# H1BR61.net
KiCad netlist of a schematic drawn in EAGLE
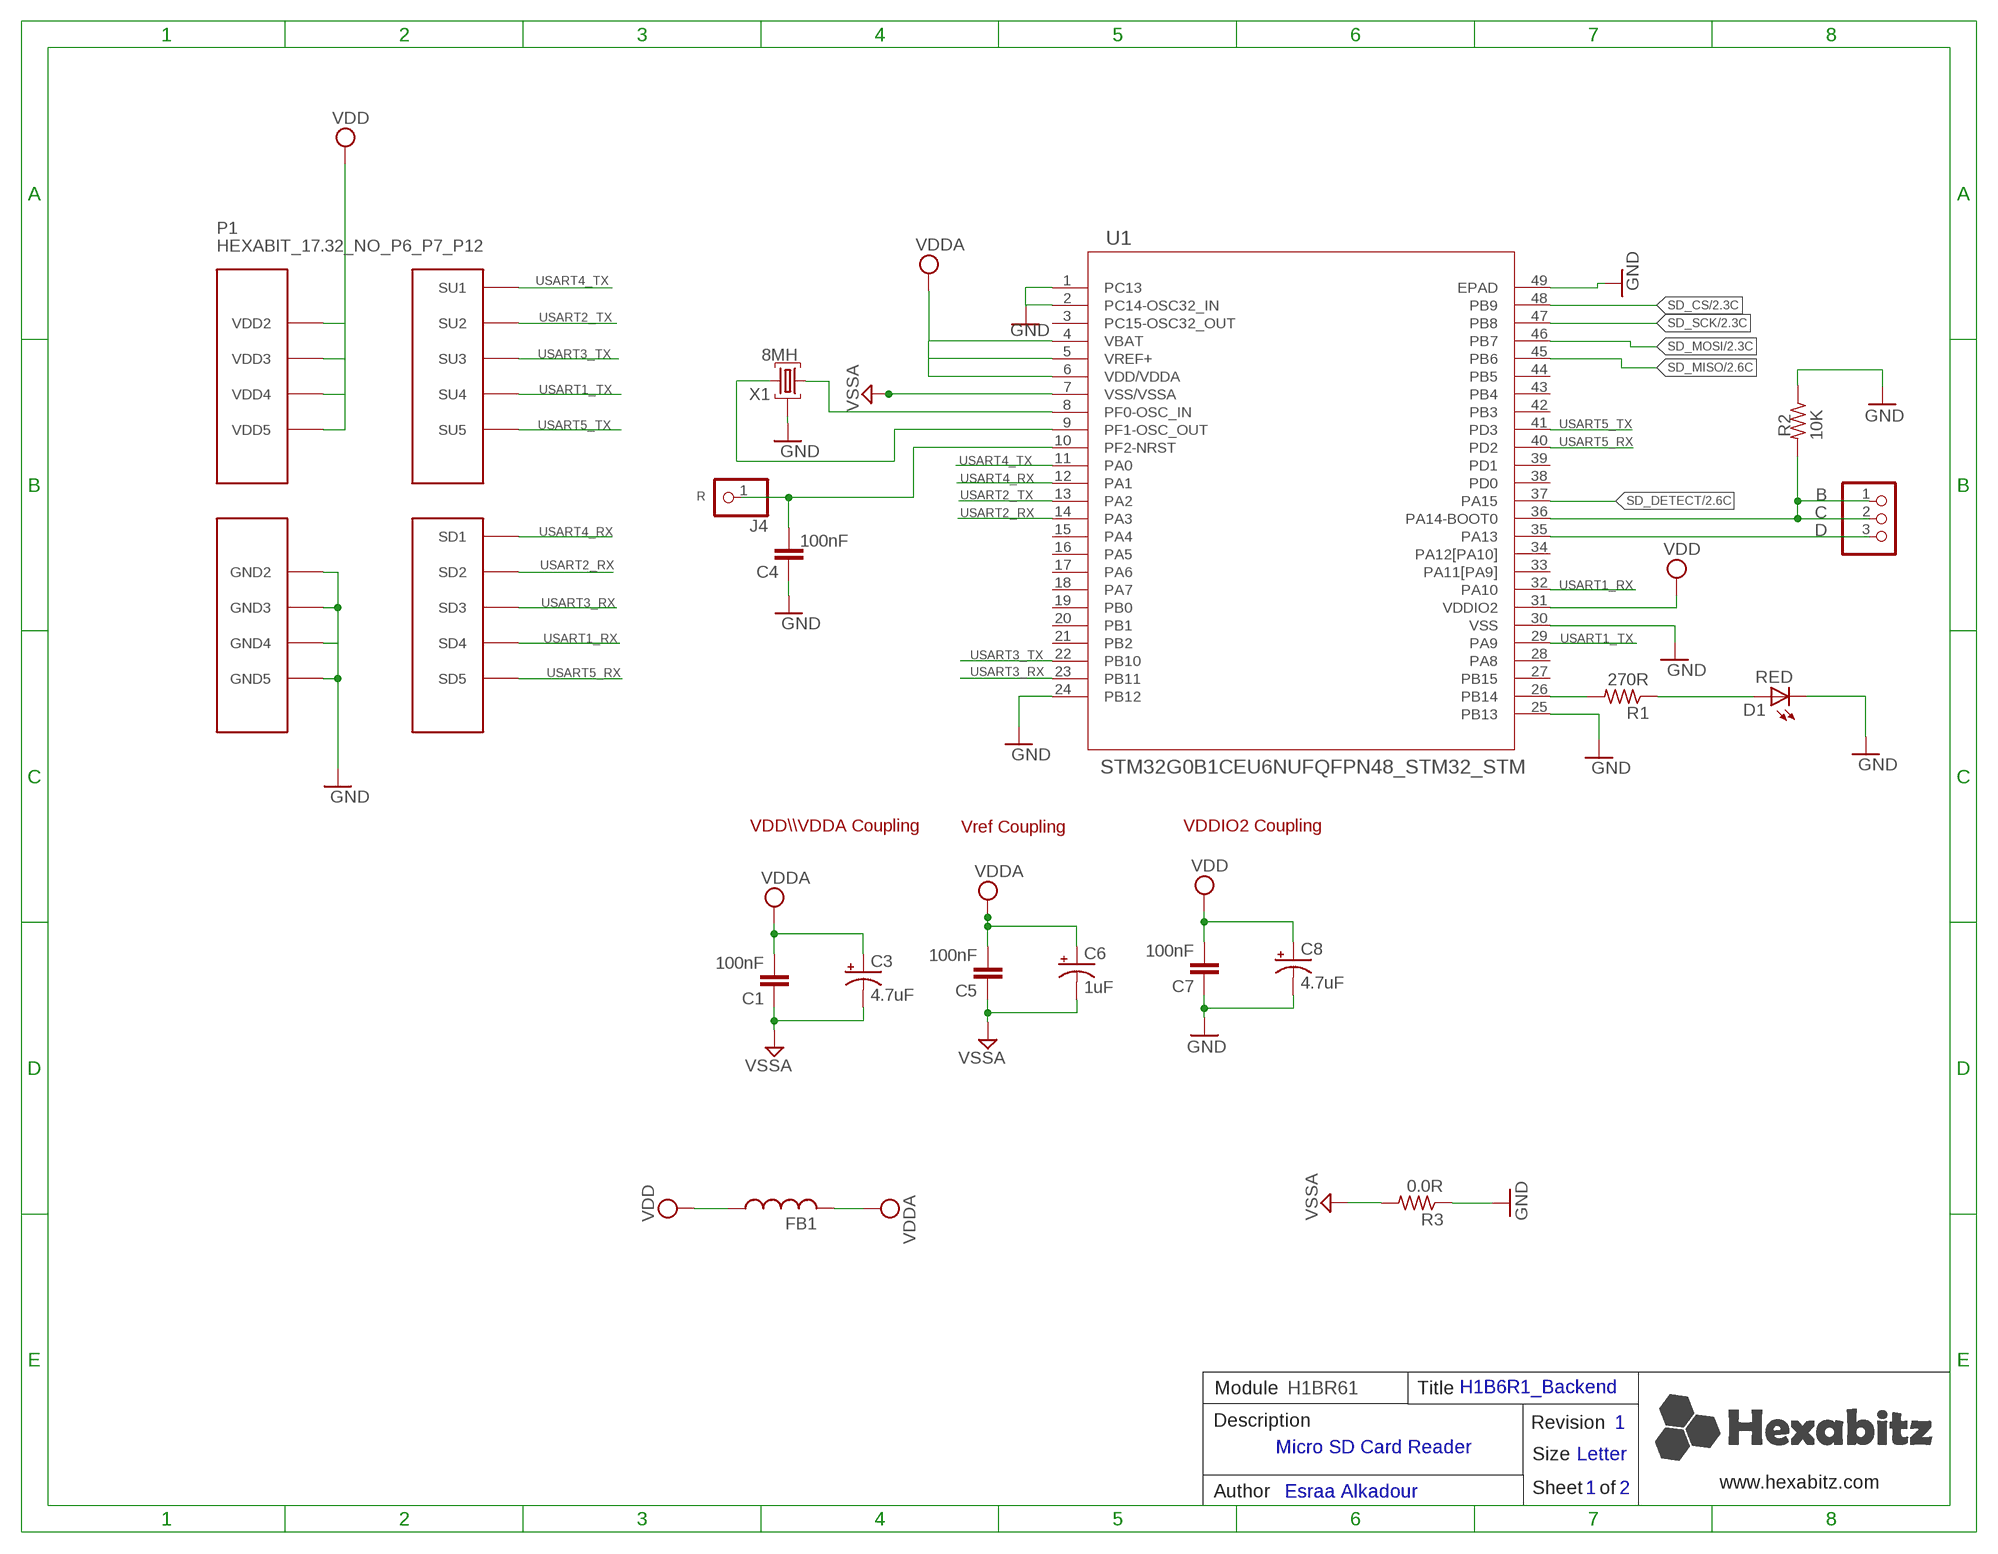
[diagram p0: schematic, sheet 1]
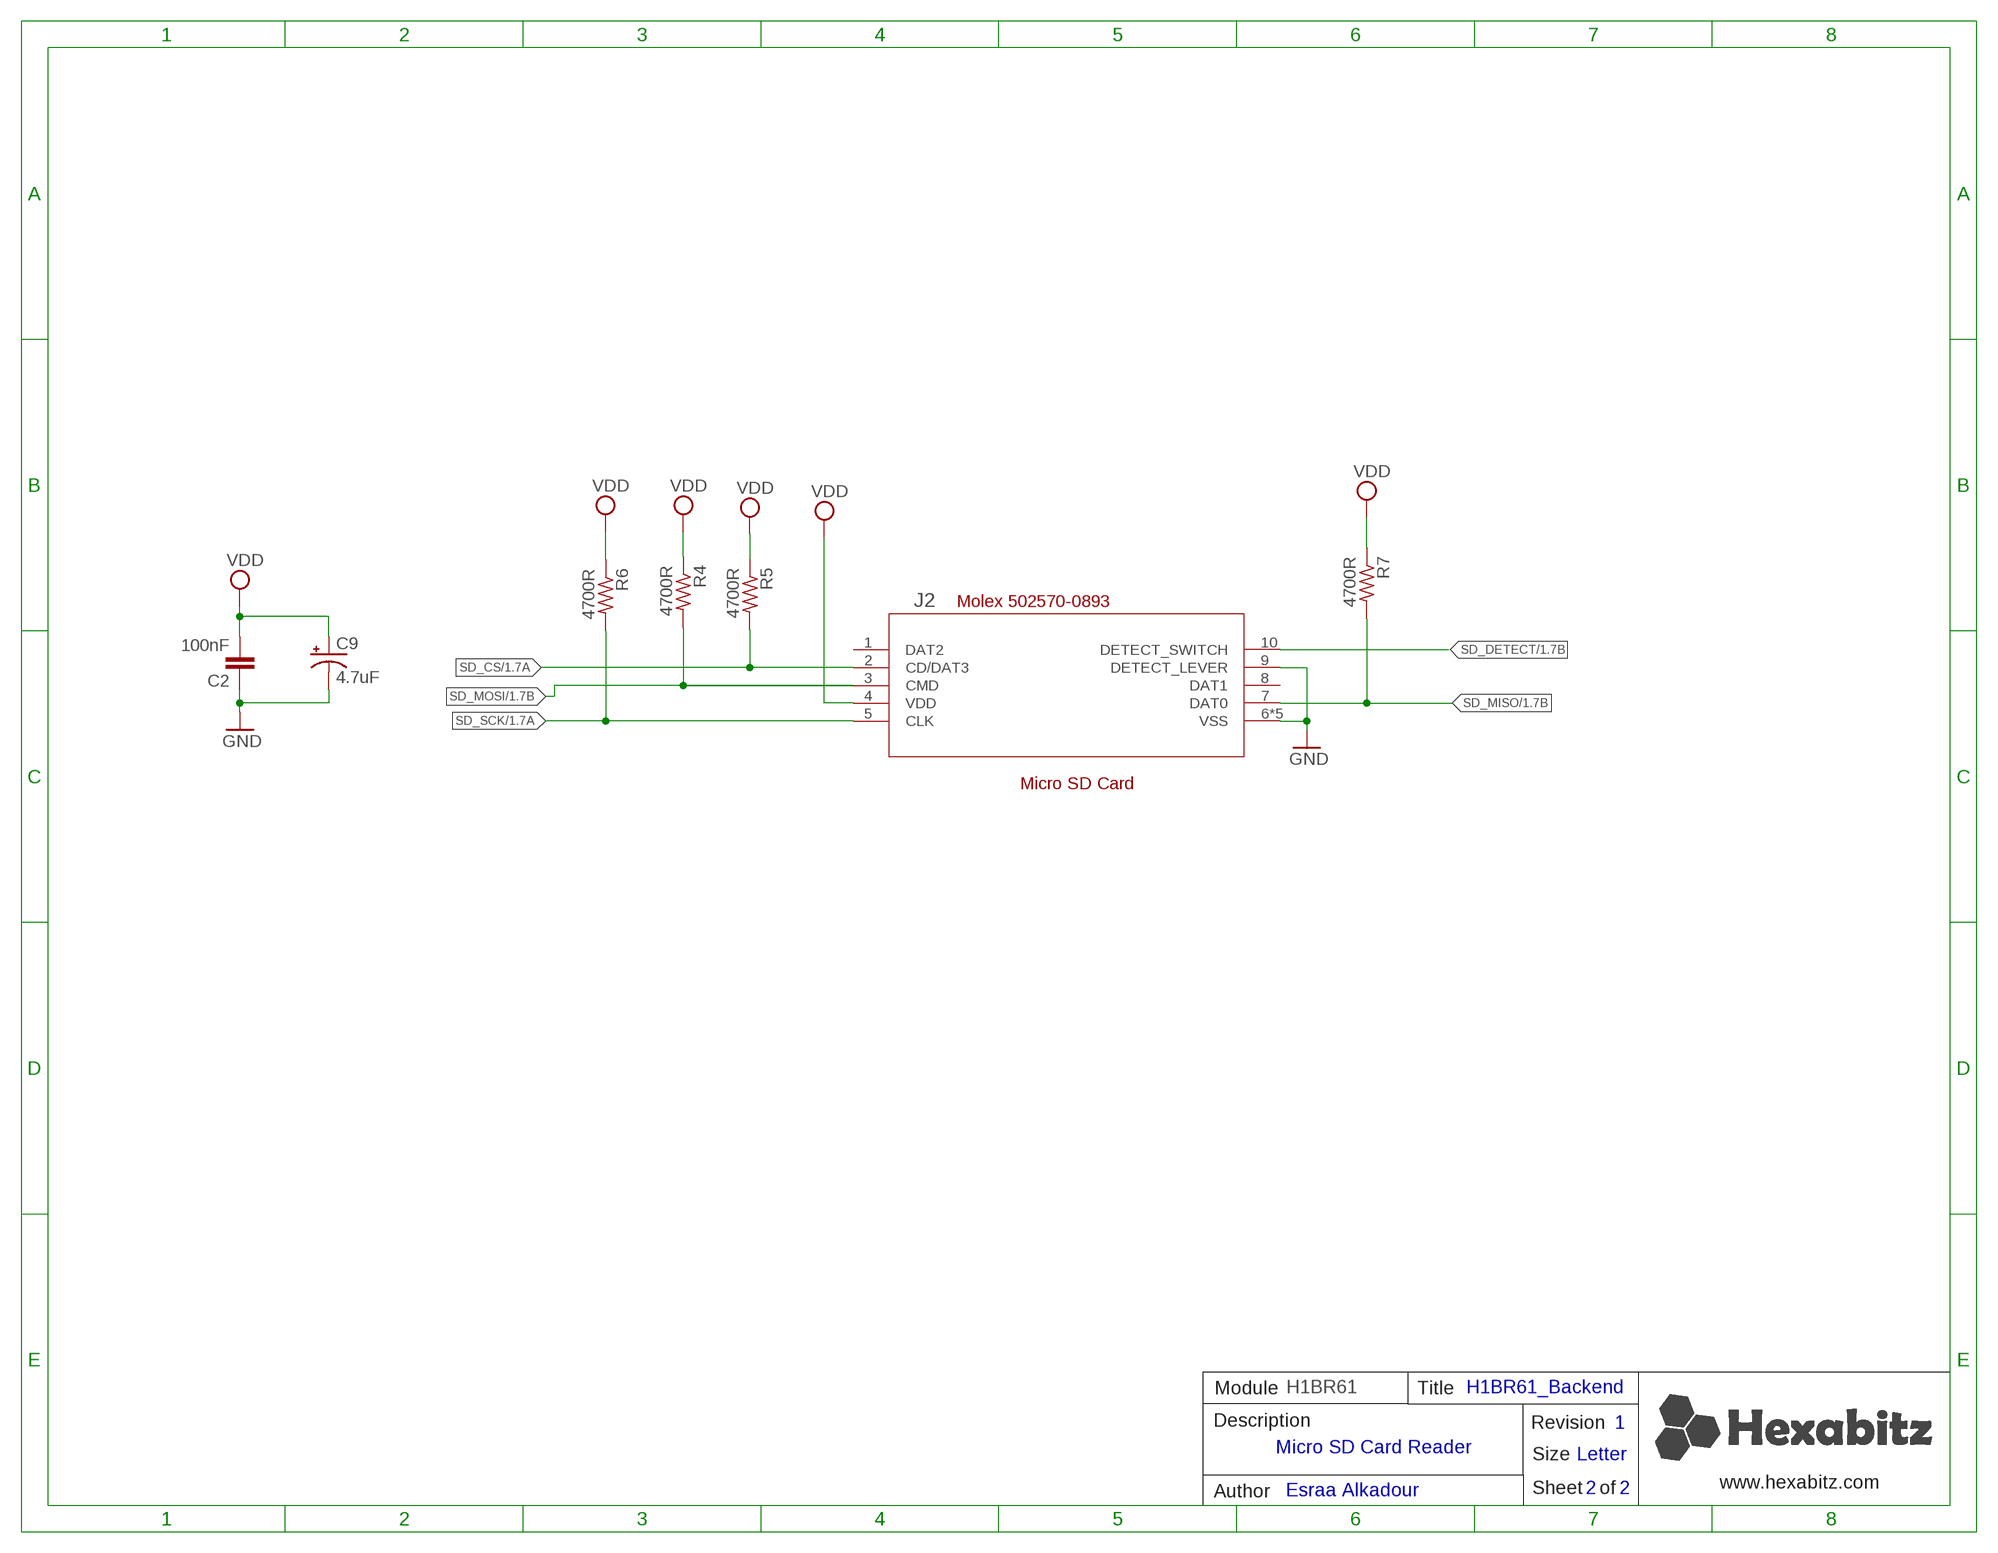
[diagram p1: schematic, sheet 2]

(export (version "E")
  (design (tool "Eeschema 10.0.6"))
  (components
    (comp (ref "C2")
      (value "100nF")
      (footprint "eagle-import:C-0603")
      (fields
        (field (name "CAPACITANCE") "100nF")
        (field (name "MFN") "AVX CORPORATION")
        (field (name "MPN") "'0603YC104K4T2A")
        (field (name "OCTOPART_URL") "'https://octopart.com/0603yc104k4t2a-avx+interconnect+%2F+elco-8120651")
        (field (name "TOLERANCE") "10%")
        (field (name "VOLTAGE_RATING") "16.0 V")
      )
      (libsource (lib "eagle-import") (part "C-0603"))
    )
    (comp (ref "C9")
      (value "4.7uF")
      (footprint "eagle-import:C-0805-POL")
      (fields
        (field (name "CAPACITANCE") "4.7uF")
        (field (name "MFN") "'Panasonic")
        (field (name "MPN") "'10TPU4R7MSI")
        (field (name "OCTOPART_URL") "https://octopart.com/10tpu4r7msi-panasonic-29487748?r=sp")
        (field (name "TOLERANCE") "20%")
        (field (name "VOLTAGE_RATING") "10.0 V")
      )
      (libsource (lib "eagle-import") (part "C-0805-POL"))
    )
    (comp (ref "J2")
      (value "5025700893502570-0893_MOL")
      (footprint "eagle-import:502570-0893_MOL")
      (fields
        (field (name "MANUFACTURER_PART_NUMBER") "5025700893")
        (field (name "COPYRIGHT") "Copyright (C) 2022 Ultra Librarian. All rights reserved.")
      )
      (libsource (lib "eagle-import") (part "5025700893502570-0893_MOL"))
    )
    (comp (ref "R4")
      (value "4700R")
      (footprint "eagle-import:R-0603")
      (fields
        (field (name "MFN") "YAGED [VA]")
        (field (name "MPN") "RC0603JR-074K7L")
        (field (name "OCTOPART_URL") "'https://octopart.com/rc0603jr-074k7l-yageo-55458509?r=sp")
        (field (name "RESISTANCE") "4700 Ohm")
        (field (name "TOLERANCE") "5%")
      )
      (libsource (lib "eagle-import") (part "R-0603"))
    )
    (comp (ref "R5")
      (value "4700R")
      (footprint "eagle-import:R-0603")
      (fields
        (field (name "MFN") "YAGED [VA]")
        (field (name "MPN") "RC0603JR-074K7L")
        (field (name "OCTOPART_URL") "'https://octopart.com/rc0603jr-074k7l-yageo-55458509?r=sp")
        (field (name "RESISTANCE") "4700 Ohm")
        (field (name "TOLERANCE") "5%")
      )
      (libsource (lib "eagle-import") (part "R-0603"))
    )
    (comp (ref "R6")
      (value "4700R")
      (footprint "eagle-import:R-0603")
      (fields
        (field (name "MFN") "YAGED [VA]")
        (field (name "MPN") "RC0603JR-074K7L")
        (field (name "OCTOPART_URL") "'https://octopart.com/rc0603jr-074k7l-yageo-55458509?r=sp")
        (field (name "RESISTANCE") "4700 Ohm")
        (field (name "TOLERANCE") "5%")
      )
      (libsource (lib "eagle-import") (part "R-0603"))
    )
    (comp (ref "R7")
      (value "4700R")
      (footprint "eagle-import:R-0603")
      (fields
        (field (name "MFN") "YAGED [VA]")
        (field (name "MPN") "RC0603JR-074K7L")
        (field (name "OCTOPART_URL") "'https://octopart.com/rc0603jr-074k7l-yageo-55458509?r=sp")
        (field (name "RESISTANCE") "4700 Ohm")
        (field (name "TOLERANCE") "5%")
      )
      (libsource (lib "eagle-import") (part "R-0603"))
    )
    (comp (ref "C1")
      (value "100nF")
      (footprint "eagle-import:C-0603")
      (fields
        (field (name "CAPACITANCE") "100nF")
        (field (name "MFN") "AVX CORPORATION")
        (field (name "MPN") "'0603YC104K4T2A")
        (field (name "OCTOPART_URL") "'https://octopart.com/0603yc104k4t2a-avx+interconnect+%2F+elco-8120651")
        (field (name "TOLERANCE") "10%")
        (field (name "VOLTAGE_RATING") "16.0 V")
      )
      (libsource (lib "eagle-import") (part "C-0603"))
    )
    (comp (ref "C3")
      (value "4.7uF")
      (footprint "eagle-import:C-0805-POL")
      (fields
        (field (name "CAPACITANCE") "4.7uF")
        (field (name "MFN") "'Panasonic")
        (field (name "MPN") "'10TPU4R7MSI")
        (field (name "OCTOPART_URL") "https://octopart.com/10tpu4r7msi-panasonic-29487748?r=sp")
        (field (name "TOLERANCE") "20%")
        (field (name "VOLTAGE_RATING") "10.0 V")
      )
      (libsource (lib "eagle-import") (part "C-0805-POL"))
    )
    (comp (ref "C4")
      (value "100nF")
      (footprint "eagle-import:C-0603")
      (fields
        (field (name "CAPACITANCE") "100nF")
        (field (name "MFN") "AVX CORPORATION")
        (field (name "MPN") "0603YC104K4T2A")
        (field (name "OCTOPART_URL") "'https://octopart.com/0603yc104k4t2a-avx+interconnect+%2F+elco-8120651")
        (field (name "TOLERANCE") "10%")
        (field (name "VOLTAGE_RATING") "16.0 V")
      )
      (libsource (lib "eagle-import") (part "C-0603"))
    )
    (comp (ref "C5")
      (value "100nF")
      (footprint "eagle-import:C-0603")
      (fields
        (field (name "CAPACITANCE") "100nF")
        (field (name "MFN") "AVX CORPORATION")
        (field (name "MPN") "'0603YC104K4T2A")
        (field (name "OCTOPART_URL") "'https://octopart.com/0603yc104k4t2a-avx+interconnect+%2F+elco-8120651")
        (field (name "TOLERANCE") "10%")
        (field (name "VOLTAGE_RATING") "16.0 V")
      )
      (libsource (lib "eagle-import") (part "C-0603"))
    )
    (comp (ref "C6")
      (value "1uF")
      (footprint "eagle-import:C-0805-POL")
      (fields
        (field (name "CAPACITANCE") "4.7uF")
        (field (name "MFN") "'YAGEO [VA]")
        (field (name "MPN") "'CC0805KKX7R7BB105")
        (field (name "OCTOPART_URL") "'https://octopart.com/cc0805kkx7r7bb105-yageo-8376555?r=sp")
        (field (name "TOLERANCE") "20%")
        (field (name "VOLTAGE_RATING") "10.0 V")
      )
      (libsource (lib "eagle-import") (part "C-0805-POL"))
    )
    (comp (ref "C7")
      (value "100nF")
      (footprint "eagle-import:C-0603")
      (fields
        (field (name "CAPACITANCE") "100nF")
        (field (name "MFN") "AVX CORPORATION")
        (field (name "MPN") "'0603YC104K4T2A")
        (field (name "OCTOPART_URL") "'https://octopart.com/0603yc104k4t2a-avx+interconnect+%2F+elco-8120651")
        (field (name "TOLERANCE") "10%")
        (field (name "VOLTAGE_RATING") "16.0 V")
      )
      (libsource (lib "eagle-import") (part "C-0603"))
    )
    (comp (ref "C8")
      (value "4.7uF")
      (footprint "eagle-import:C-0805-POL")
      (fields
        (field (name "CAPACITANCE") "1.00uF")
        (field (name "MFN") "'Panasonic")
        (field (name "MPN") "'10TPU4R7MSI")
        (field (name "OCTOPART_URL") "https://octopart.com/10tpu4r7msi-panasonic-29487748?r=sp")
        (field (name "TOLERANCE") "10%")
        (field (name "VOLTAGE_RATING") "16.0 V")
      )
      (libsource (lib "eagle-import") (part "C-0805-POL"))
    )
    (comp (ref "D1")
      (value "RED")
      (footprint "eagle-import:VLMS1300-GS08")
      (fields (field (name "MPN") "VLMS1300-GS08"))
      (libsource (lib "eagle-import") (part "VLMS1300-GS08"))
    )
    (comp (ref "FB1")
      (value "FB-TDK_MMZ1608Y300B")
      (footprint "eagle-import:FB-TDK_MMZ1608Y300B")
      (fields
        (field (name "MFN") "TDK ")
        (field (name "MPN") "MMZ1608Y300BTA00")
        (field (name "OCTOPART_URL") "https://octopart.com/mmz1608y300bta00-tdk-7906990?r=sp")
      )
      (libsource (lib "eagle-import") (part "FB-TDK_MMZ1608Y300B"))
    )
    (comp (ref "J4")
      (value "PINHD-1X1")
      (footprint "eagle-import:1X01")
      (fields (field (name "MPN") "87227-1"))
      (libsource (lib "eagle-import") (part "PINHD-1X1"))
    )
    (comp (ref "JP1")
      (value "PINHD-1X3")
      (footprint "eagle-import:1X03")
      (libsource (lib "eagle-import") (part "PINHD-1X3"))
    )
    (comp (ref "P1")
      (value "HEXABIT_17.32_NO_P6_P7_P12")
      (footprint "eagle-import:HEXABIT_17.32_NO_P6_P7_P12")
      (libsource (lib "eagle-import") (part "HEXABIT_?_NO_P6_P7_P1217.32"))
    )
    (comp (ref "R1")
      (value "270R")
      (footprint "eagle-import:R-0603")
      (fields
        (field (name "MFN") "'Panasonic")
        (field (name "MPN") "'ERJ-3GEYJ271V")
        (field (name "OCTOPART_URL") "https://octopart.com/erj-3geyj271v-panasonic-55560546?r=sp")
        (field (name "RESISTANCE") "270R")
      )
      (libsource (lib "eagle-import") (part "R-0603"))
    )
    (comp (ref "R2")
      (value "10K")
      (footprint "eagle-import:R-0603")
      (fields
        (field (name "MFN") "Vishay")
        (field (name "MPN") "'060300J0103T5E")
        (field (name "OCTOPART_URL") "https://octopart.com/search?q=060300J0103T5E&currency=USD&specs=0")
        (field (name "RESISTANCE") "10K")
      )
      (libsource (lib "eagle-import") (part "R-0603"))
    )
    (comp (ref "R3")
      (value "0.0R")
      (footprint "eagle-import:R-0603")
      (fields
        (field (name "MFN") "YAGEO [VR]")
        (field (name "MPN") "RC0603JR-070RL")
        (field (name "OCTOPART_URL") "https://octopart.com/rc0603jr-070rl-yageo-1241539?r=sp")
        (field (name "RESISTANCE") "0R")
      )
      (libsource (lib "eagle-import") (part "R-0603"))
    )
    (comp (ref "U1")
      (value "STM32G0B1CEU6NUFQFPN48_STM32_STM")
      (footprint "eagle-import:UFQFPN48_STM32_STM")
      (fields
        (field (name "MPN") "STM32G0B1CEU6N")
        (field (name "OCTOPART_URL") "https://octopart.com/stm32g0b1ceu6n-stmicroelectronics-116364672?r=sp")
        (field (name "COPYRIGHT") "Copyright (C) 2022 Ultra Librarian. All rights reserved.")
      )
      (libsource (lib "eagle-import") (part "STM32G0B1CEU6NUFQFPN48_STM32_STM"))
    )
    (comp (ref "X1")
      (value "8MH")
      (footprint "eagle-import:XTALL_CSTCE8M00G52")
      (fields
        (field (name "MPN") "CSTCE8M00G52Z-R0")
        (field (name "MPN_1") "CSTNE8M00G550000R0")
        (field (name "OCTOPART_URL") "https://octopart.com/cstne8m00g550000r0-murata-91406934?r=sp")
      )
      (libsource (lib "eagle-import") (part "XTALL_CSTCE8M00G52"))
    )
  )
  (nets
    (net (code "1") (name "C") (class "Default")
      (node (ref "JP1") (pin "1") (pinfunction "1_1") (pintype "passive"))
      (node (ref "JP1") (pin "2") (pinfunction "2_2") (pintype "passive"))
      (node (ref "R2") (pin "2") (pinfunction "2_2") (pintype "passive"))
      (node (ref "U1") (pin "36") (pinfunction "PA14-BOOT0_36") (pintype "bidirectional"))
    )
    (net (code "2") (name "D") (class "Default")
      (node (ref "JP1") (pin "3") (pinfunction "3_3") (pintype "passive"))
      (node (ref "U1") (pin "35") (pinfunction "PA13_35") (pintype "bidirectional"))
    )
    (net (code "3") (name "GND") (class "Default")
      (node (ref "C2") (pin "1") (pinfunction "1_1") (pintype "passive"))
      (node (ref "C4") (pin "1") (pinfunction "1_1") (pintype "passive"))
      (node (ref "C7") (pin "1") (pinfunction "1_1") (pintype "passive"))
      (node (ref "C8") (pin "2") (pinfunction "-_2") (pintype "passive"))
      (node (ref "C9") (pin "2") (pinfunction "-_2") (pintype "passive"))
      (node (ref "D1") (pin "C") (pinfunction "C_C") (pintype "passive"))
      (node (ref "J2") (pin "11") (pinfunction "VSS_11") (pintype "passive"))
      (node (ref "J2") (pin "12") (pinfunction "VSS_12") (pintype "passive"))
      (node (ref "J2") (pin "13") (pinfunction "VSS_13") (pintype "passive"))
      (node (ref "J2") (pin "14") (pinfunction "VSS_14") (pintype "passive"))
      (node (ref "J2") (pin "6") (pinfunction "VSS_6") (pintype "passive"))
      (node (ref "J2") (pin "9") (pinfunction "DETECT_LEVER_9") (pintype "passive"))
      (node (ref "P1") (pin "PAD_PD10") (pinfunction "GND4_PAD_PD10") (pintype "power_in"))
      (node (ref "P1") (pin "PAD_PD11") (pinfunction "GND5_PAD_PD11") (pintype "power_in"))
      (node (ref "P1") (pin "PAD_PD8") (pinfunction "GND2_PAD_PD8") (pintype "power_in"))
      (node (ref "P1") (pin "PAD_PD9") (pinfunction "GND3_PAD_PD9") (pintype "power_in"))
      (node (ref "R2") (pin "1") (pinfunction "1_1") (pintype "passive"))
      (node (ref "R3") (pin "1") (pinfunction "1_1") (pintype "passive"))
      (node (ref "U1") (pin "1") (pinfunction "PC13_1") (pintype "bidirectional"))
      (node (ref "U1") (pin "2") (pinfunction "PC14-OSC32_IN_2") (pintype "bidirectional"))
      (node (ref "U1") (pin "24") (pinfunction "PB12_24") (pintype "bidirectional"))
      (node (ref "U1") (pin "25") (pinfunction "PB13_25") (pintype "bidirectional"))
      (node (ref "U1") (pin "30") (pinfunction "VSS_30") (pintype "passive"))
      (node (ref "U1") (pin "49") (pinfunction "EPAD_49") (pintype "passive"))
      (node (ref "X1") (pin "P$2") (pinfunction "2_P$2") (pintype "passive"))
    )
    (net (code "4") (name "GND1") (class "Default")
      (node (ref "C1") (pin "1") (pinfunction "1_1") (pintype "passive"))
      (node (ref "C3") (pin "2") (pinfunction "-_2") (pintype "passive"))
      (node (ref "C5") (pin "1") (pinfunction "1_1") (pintype "passive"))
      (node (ref "C6") (pin "2") (pinfunction "-_2") (pintype "passive"))
      (node (ref "R3") (pin "2") (pinfunction "2_2") (pintype "passive"))
      (node (ref "U1") (pin "7") (pinfunction "VSS/VSSA_7") (pintype "passive"))
    )
    (net (code "5") (name "Net-(D1-PadA)") (class "Default")
      (node (ref "D1") (pin "A") (pinfunction "A_A") (pintype "passive"))
      (node (ref "R1") (pin "1") (pinfunction "1_1") (pintype "passive"))
    )
    (net (code "6") (name "Net-(U1-PB14)") (class "Default")
      (node (ref "R1") (pin "2") (pinfunction "2_2") (pintype "passive"))
      (node (ref "U1") (pin "26") (pinfunction "PB14_26") (pintype "bidirectional"))
    )
    (net (code "7") (name "Net-(U1-PF0-OSC_IN)") (class "Default")
      (node (ref "U1") (pin "8") (pinfunction "PF0-OSC_IN_8") (pintype "bidirectional"))
      (node (ref "X1") (pin "P$3") (pinfunction "3_P$3") (pintype "passive"))
    )
    (net (code "8") (name "Net-(U1-PF1-OSC_OUT)") (class "Default")
      (node (ref "U1") (pin "9") (pinfunction "PF1-OSC_OUT_9") (pintype "bidirectional"))
      (node (ref "X1") (pin "P$1") (pinfunction "1_P$1") (pintype "passive"))
    )
    (net (code "9") (name "R") (class "Default")
      (node (ref "C4") (pin "2") (pinfunction "2_2") (pintype "passive"))
      (node (ref "J4") (pin "1") (pinfunction "1_1") (pintype "passive"))
      (node (ref "U1") (pin "10") (pinfunction "PF2-NRST_10") (pintype "bidirectional"))
    )
    (net (code "10") (name "SD_CS") (class "Default")
      (node (ref "J2") (pin "2") (pinfunction "CD/DAT3_2") (pintype "passive"))
      (node (ref "R5") (pin "2") (pinfunction "2_2") (pintype "passive"))
      (node (ref "U1") (pin "48") (pinfunction "PB9_48") (pintype "bidirectional"))
    )
    (net (code "11") (name "SD_DETECT") (class "Default")
      (node (ref "J2") (pin "10") (pinfunction "DETECT_SWITCH_10") (pintype "passive"))
      (node (ref "U1") (pin "37") (pinfunction "PA15_37") (pintype "bidirectional"))
    )
    (net (code "12") (name "SD_MISO") (class "Default")
      (node (ref "J2") (pin "7") (pinfunction "DAT0_7") (pintype "bidirectional"))
      (node (ref "R7") (pin "2") (pinfunction "2_2") (pintype "passive"))
      (node (ref "U1") (pin "45") (pinfunction "PB6_45") (pintype "bidirectional"))
    )
    (net (code "13") (name "SD_MOSI") (class "Default")
      (node (ref "J2") (pin "3") (pinfunction "CMD_3") (pintype "passive"))
      (node (ref "R4") (pin "2") (pinfunction "2_2") (pintype "passive"))
      (node (ref "U1") (pin "46") (pinfunction "PB7_46") (pintype "bidirectional"))
    )
    (net (code "14") (name "SD_SCK") (class "Default")
      (node (ref "J2") (pin "5") (pinfunction "CLK_5") (pintype "passive"))
      (node (ref "R6") (pin "2") (pinfunction "2_2") (pintype "passive"))
      (node (ref "U1") (pin "47") (pinfunction "PB8_47") (pintype "bidirectional"))
    )
    (net (code "15") (name "USART1_RX") (class "Default")
      (node (ref "P1") (pin "PAD_PD4") (pinfunction "SD4_PAD_PD4") (pintype "bidirectional"))
      (node (ref "U1") (pin "32") (pinfunction "PA10_32") (pintype "bidirectional"))
    )
    (net (code "16") (name "USART1_TX") (class "Default")
      (node (ref "P1") (pin "PAD_PU4") (pinfunction "SU4_PAD_PU4") (pintype "bidirectional"))
      (node (ref "U1") (pin "29") (pinfunction "PA9_29") (pintype "bidirectional"))
    )
    (net (code "17") (name "USART2_RX") (class "Default")
      (node (ref "P1") (pin "PAD_PD2") (pinfunction "SD2_PAD_PD2") (pintype "bidirectional"))
      (node (ref "U1") (pin "14") (pinfunction "PA3_14") (pintype "bidirectional"))
    )
    (net (code "18") (name "USART2_TX") (class "Default")
      (node (ref "P1") (pin "PAD_PU2") (pinfunction "SU2_PAD_PU2") (pintype "bidirectional"))
      (node (ref "U1") (pin "13") (pinfunction "PA2_13") (pintype "bidirectional"))
    )
    (net (code "19") (name "USART3_RX") (class "Default")
      (node (ref "P1") (pin "PAD_PD3") (pinfunction "SD3_PAD_PD3") (pintype "bidirectional"))
      (node (ref "U1") (pin "23") (pinfunction "PB11_23") (pintype "bidirectional"))
    )
    (net (code "20") (name "USART3_TX") (class "Default")
      (node (ref "P1") (pin "PAD_PU3") (pinfunction "SU3_PAD_PU3") (pintype "bidirectional"))
      (node (ref "U1") (pin "22") (pinfunction "PB10_22") (pintype "bidirectional"))
    )
    (net (code "21") (name "USART4_RX") (class "Default")
      (node (ref "P1") (pin "PAD_PD1") (pinfunction "SD1_PAD_PD1") (pintype "bidirectional"))
      (node (ref "U1") (pin "12") (pinfunction "PA1_12") (pintype "bidirectional"))
    )
    (net (code "22") (name "USART4_TX") (class "Default")
      (node (ref "P1") (pin "PAD_PU1") (pinfunction "SU1_PAD_PU1") (pintype "bidirectional"))
      (node (ref "U1") (pin "11") (pinfunction "PA0_11") (pintype "bidirectional"))
    )
    (net (code "23") (name "USART5_RX") (class "Default")
      (node (ref "P1") (pin "PAD_PD5") (pinfunction "SD5_PAD_PD5") (pintype "bidirectional"))
      (node (ref "U1") (pin "40") (pinfunction "PD2_40") (pintype "bidirectional"))
    )
    (net (code "24") (name "USART5_TX") (class "Default")
      (node (ref "P1") (pin "PAD_PU5") (pinfunction "SU5_PAD_PU5") (pintype "bidirectional"))
      (node (ref "U1") (pin "41") (pinfunction "PD3_41") (pintype "bidirectional"))
    )
    (net (code "25") (name "VCC") (class "Default")
      (node (ref "C1") (pin "2") (pinfunction "2_2") (pintype "passive"))
      (node (ref "C3") (pin "1") (pinfunction "+_1") (pintype "passive"))
      (node (ref "C5") (pin "2") (pinfunction "2_2") (pintype "passive"))
      (node (ref "C6") (pin "1") (pinfunction "+_1") (pintype "passive"))
      (node (ref "FB1") (pin "2") (pinfunction "2_2") (pintype "passive"))
      (node (ref "U1") (pin "4") (pinfunction "VBAT_4") (pintype "power_in"))
      (node (ref "U1") (pin "5") (pinfunction "VREF+_5") (pintype "power_in"))
      (node (ref "U1") (pin "6") (pinfunction "VDD/VDDA_6") (pintype "power_in"))
    )
    (net (code "26") (name "VDD") (class "Default")
      (node (ref "C2") (pin "2") (pinfunction "2_2") (pintype "passive"))
      (node (ref "C7") (pin "2") (pinfunction "2_2") (pintype "passive"))
      (node (ref "C8") (pin "1") (pinfunction "+_1") (pintype "passive"))
      (node (ref "C9") (pin "1") (pinfunction "+_1") (pintype "passive"))
      (node (ref "FB1") (pin "1") (pinfunction "1_1") (pintype "passive"))
      (node (ref "J2") (pin "4") (pinfunction "VDD_4") (pintype "power_in"))
      (node (ref "P1") (pin "PAD_PU10") (pinfunction "VDD4_PAD_PU10") (pintype "power_in"))
      (node (ref "P1") (pin "PAD_PU11") (pinfunction "VDD5_PAD_PU11") (pintype "power_in"))
      (node (ref "P1") (pin "PAD_PU8") (pinfunction "VDD2_PAD_PU8") (pintype "power_in"))
      (node (ref "P1") (pin "PAD_PU9") (pinfunction "VDD3_PAD_PU9") (pintype "power_in"))
      (node (ref "R4") (pin "1") (pinfunction "1_1") (pintype "passive"))
      (node (ref "R5") (pin "1") (pinfunction "1_1") (pintype "passive"))
      (node (ref "R6") (pin "1") (pinfunction "1_1") (pintype "passive"))
      (node (ref "R7") (pin "1") (pinfunction "1_1") (pintype "passive"))
      (node (ref "U1") (pin "31") (pinfunction "VDDIO2_31") (pintype "power_in"))
    )
    (net (code "27") (name "unconnected-(J2-DAT1-Pad8)") (class "Default")
      (node (ref "J2") (pin "8") (pinfunction "DAT1_8") (pintype "bidirectional"))
    )
    (net (code "28") (name "unconnected-(J2-DAT2-Pad1)") (class "Default")
      (node (ref "J2") (pin "1") (pinfunction "DAT2_1") (pintype "bidirectional"))
    )
    (net (code "29") (name "unconnected-(U1-PA4-Pad15)") (class "Default")
      (node (ref "U1") (pin "15") (pinfunction "PA4_15") (pintype "bidirectional"))
    )
    (net (code "30") (name "unconnected-(U1-PA5-Pad16)") (class "Default")
      (node (ref "U1") (pin "16") (pinfunction "PA5_16") (pintype "bidirectional"))
    )
    (net (code "31") (name "unconnected-(U1-PA6-Pad17)") (class "Default")
      (node (ref "U1") (pin "17") (pinfunction "PA6_17") (pintype "bidirectional"))
    )
    (net (code "32") (name "unconnected-(U1-PA7-Pad18)") (class "Default")
      (node (ref "U1") (pin "18") (pinfunction "PA7_18") (pintype "bidirectional"))
    )
    (net (code "33") (name "unconnected-(U1-PA8-Pad28)") (class "Default")
      (node (ref "U1") (pin "28") (pinfunction "PA8_28") (pintype "bidirectional"))
    )
    (net (code "34") (name "unconnected-(U1-PA11[PA9]-Pad33)") (class "Default")
      (node (ref "U1") (pin "33") (pinfunction "PA11[PA9]_33") (pintype "bidirectional"))
    )
    (net (code "35") (name "unconnected-(U1-PA12[PA10]-Pad34)") (class "Default")
      (node (ref "U1") (pin "34") (pinfunction "PA12[PA10]_34") (pintype "bidirectional"))
    )
    (net (code "36") (name "unconnected-(U1-PB0-Pad19)") (class "Default")
      (node (ref "U1") (pin "19") (pinfunction "PB0_19") (pintype "bidirectional"))
    )
    (net (code "37") (name "unconnected-(U1-PB1-Pad20)") (class "Default")
      (node (ref "U1") (pin "20") (pinfunction "PB1_20") (pintype "bidirectional"))
    )
    (net (code "38") (name "unconnected-(U1-PB2-Pad21)") (class "Default")
      (node (ref "U1") (pin "21") (pinfunction "PB2_21") (pintype "bidirectional"))
    )
    (net (code "39") (name "unconnected-(U1-PB3-Pad42)") (class "Default")
      (node (ref "U1") (pin "42") (pinfunction "PB3_42") (pintype "bidirectional"))
    )
    (net (code "40") (name "unconnected-(U1-PB4-Pad43)") (class "Default")
      (node (ref "U1") (pin "43") (pinfunction "PB4_43") (pintype "bidirectional"))
    )
    (net (code "41") (name "unconnected-(U1-PB5-Pad44)") (class "Default")
      (node (ref "U1") (pin "44") (pinfunction "PB5_44") (pintype "bidirectional"))
    )
    (net (code "42") (name "unconnected-(U1-PB15-Pad27)") (class "Default")
      (node (ref "U1") (pin "27") (pinfunction "PB15_27") (pintype "bidirectional"))
    )
    (net (code "43") (name "unconnected-(U1-PC15-OSC32_OUT-Pad3)") (class "Default")
      (node (ref "U1") (pin "3") (pinfunction "PC15-OSC32_OUT_3") (pintype "bidirectional"))
    )
    (net (code "44") (name "unconnected-(U1-PD0-Pad38)") (class "Default")
      (node (ref "U1") (pin "38") (pinfunction "PD0_38") (pintype "bidirectional"))
    )
    (net (code "45") (name "unconnected-(U1-PD1-Pad39)") (class "Default")
      (node (ref "U1") (pin "39") (pinfunction "PD1_39") (pintype "bidirectional"))
    )
  )
)
